# BLE_MCU_Watch_Dog_and_Reset_EEPROM_Buzze.net
KiCad netlist of a schematic drawn in Altium Designer
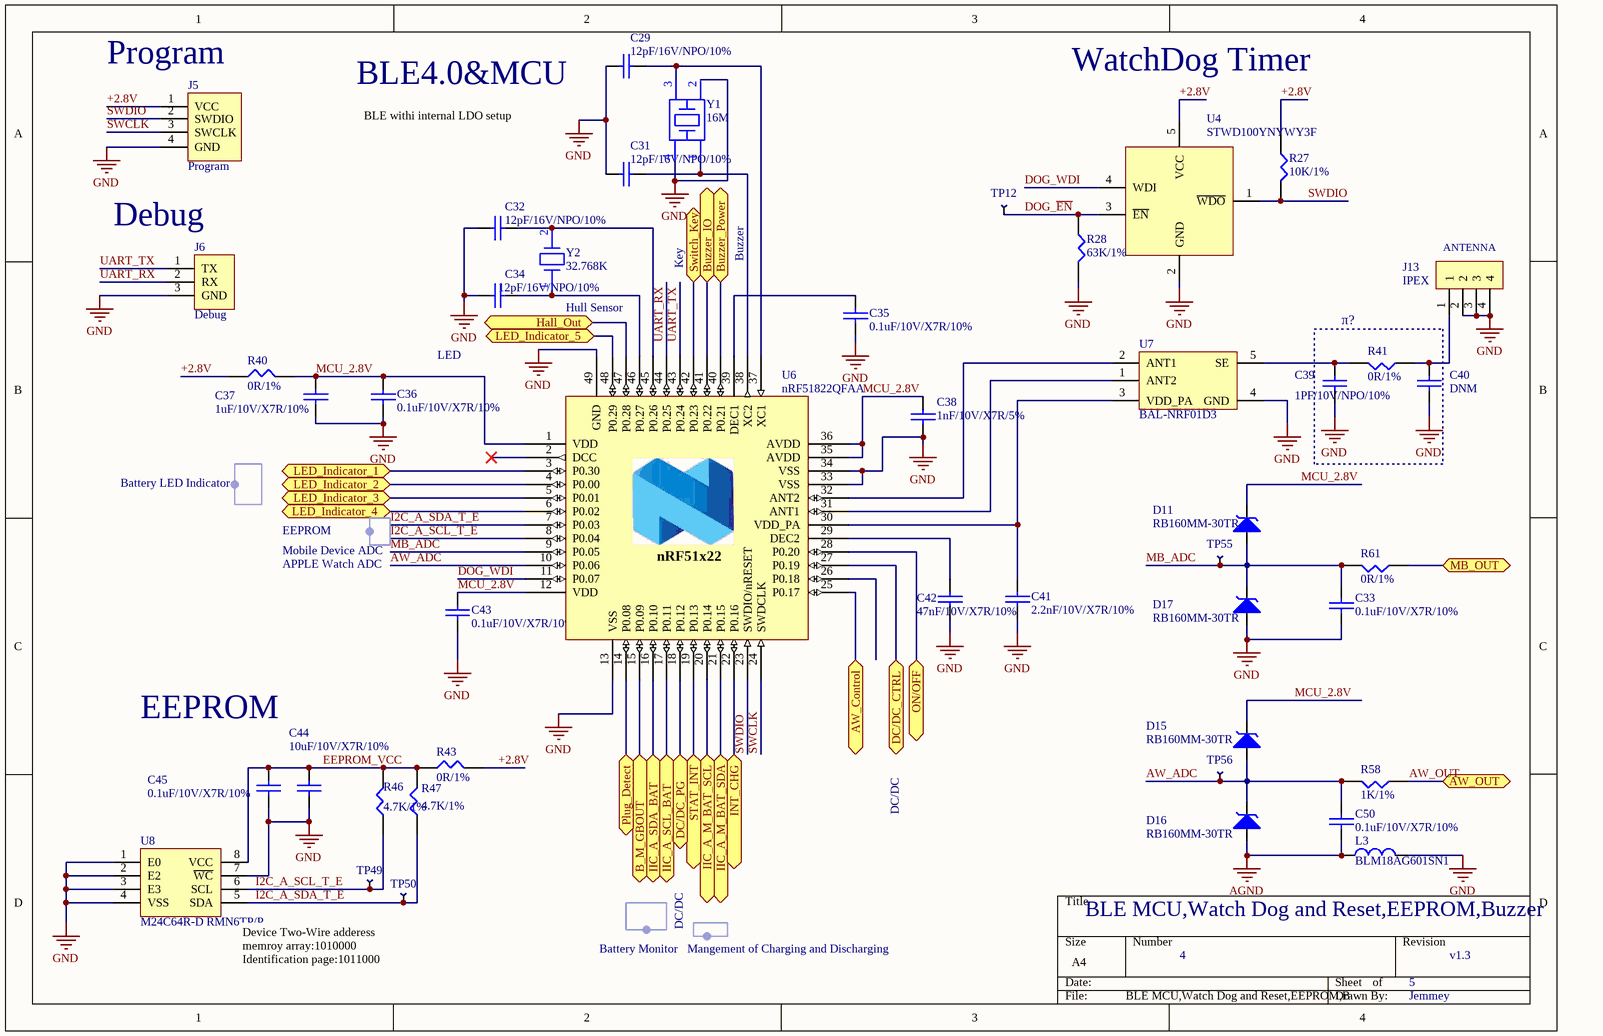
[diagram p0: BLE MCU,Watch Dog and Reset,EEPROM,Buzzer.SchDoc]

(export (version "E")
  (design (tool "Eeschema 10.0.6"))
  (components
    (comp (ref "C29")
      (value "12pF/16V/NPO/10%")
      (footprint "0402C")
      (description "厂家：Murata，型号：GRM1555C1H120JA01D")
      (libsource (lib "Amber") (part "CAP"))
    )
    (comp (ref "C31")
      (value "12pF/16V/NPO/10%")
      (footprint "0402C")
      (description "厂家：Murata，型号：GRM1555C1H120JA01D")
      (libsource (lib "Amber") (part "CAP"))
    )
    (comp (ref "C32")
      (value "12pF/16V/NPO/10%")
      (footprint "0402C")
      (description "厂家：Murata，型号：GRM1555C1H120JA01D")
      (libsource (lib "Amber") (part "CAP"))
    )
    (comp (ref "C33")
      (value "0.1uF/10V/X7R/10%")
      (footprint "0402C")
      (description "厂家：Murata，型号：GRM155R71A104KA01D")
      (libsource (lib "*") (part "CAP"))
    )
    (comp (ref "C34")
      (value "12pF/16V/NPO/10%")
      (footprint "0402C")
      (description "厂家：Murata，型号：GRM1555C1H120JA01D")
      (libsource (lib "Amber") (part "CAP"))
    )
    (comp (ref "C35")
      (value "0.1uF/10V/X7R/10%")
      (footprint "0402C")
      (description "厂家：Murata，型号：GRM155R71A104KA01D")
      (libsource (lib "Amber") (part "CAP"))
    )
    (comp (ref "C36")
      (value "0.1uF/10V/X7R/10%")
      (footprint "0402C")
      (description "厂家：Murata，型号：GRM155R71A104KA01D")
      (libsource (lib "Amber") (part "CAP"))
    )
    (comp (ref "C37")
      (value "1uF/10V/X7R/10%")
      (footprint "0402C")
      (description "厂家：Murata，型号：GRM155R61C105KA12D")
      (libsource (lib "Amber") (part "CAP"))
    )
    (comp (ref "C38")
      (value "1nF/10V/X7R/5%")
      (footprint "0402C")
      (description "厂家：Murata，型号：GRM1555C1H102JA01D")
      (libsource (lib "Amber") (part "CAP"))
    )
    (comp (ref "C39")
      (value "1PF/10V/NPO/10%")
      (footprint "0402C")
      (description "厂家：Murata，型号：GRM1555C1H1R0BA01D")
      (libsource (lib "*") (part "CAP"))
    )
    (comp (ref "C40")
      (value "DNM")
      (footprint "0402C")
      (description "None")
      (libsource (lib "*") (part "CAP"))
    )
    (comp (ref "C41")
      (value "2.2nF/10V/X7R/10%")
      (footprint "0402C")
      (description "厂家：Murata，型号：GRM155R71H222KA01D")
      (libsource (lib "Amber") (part "CAP"))
    )
    (comp (ref "C42")
      (value "47nF/10V/X7R/10%")
      (footprint "0402C")
      (description "厂家：Murata，型号：GRM155R71H473KE14D")
      (libsource (lib "Amber") (part "CAP"))
    )
    (comp (ref "C43")
      (value "0.1uF/10V/X7R/10%")
      (footprint "0402C")
      (description "厂家：Murata，型号：GRM155R71A104KA01D")
      (libsource (lib "Amber") (part "CAP"))
    )
    (comp (ref "C44")
      (value "10uF/10V/X7R/10%")
      (footprint "0603C")
      (description "厂家：Murata，型号：GRM188R61A106KE69D")
      (libsource (lib "*") (part "CAP"))
    )
    (comp (ref "C45")
      (value "0.1uF/10V/X7R/10%")
      (footprint "0402C")
      (description "厂家：Murata，型号：GRM155R71A104KA01D")
      (libsource (lib "*") (part "CAP"))
    )
    (comp (ref "C50")
      (value "0.1uF/10V/X7R/10%")
      (footprint "0402C")
      (description "厂家：Murata，型号：GRM155R71A104KA01D")
      (libsource (lib "*") (part "CAP"))
    )
    (comp (ref "D11")
      (value "RB160MM-30TR")
      (footprint "DO-214AC")
      (description "厂家：ROHM，型号：RB160MM-30TR")
      (libsource (lib "Moji_Assenbly Test") (part "Schottky barrier rectifier"))
    )
    (comp (ref "D15")
      (value "RB160MM-30TR")
      (footprint "DO-214AC")
      (description "厂家：ROHM，型号：RB160MM-30TR")
      (libsource (lib "Moji_Assenbly Test") (part "Schottky barrier rectifier"))
    )
    (comp (ref "D16")
      (value "RB160MM-30TR")
      (footprint "DO-214AC")
      (description "厂家：ROHM，型号：RB160MM-30TR")
      (libsource (lib "Moji_Assenbly Test") (part "Schottky barrier rectifier"))
    )
    (comp (ref "D17")
      (value "RB160MM-30TR")
      (footprint "DO-214AC")
      (description "厂家：ROHM，型号：RB160MM-30TR")
      (libsource (lib "Moji_Assenbly Test") (part "Schottky barrier rectifier"))
    )
    (comp (ref "J5")
      (value "Program")
      (footprint "PROGRAM - 1.27")
      (description "厂家：暂定，型号：暂定")
      (libsource (lib "Amber") (part "Program"))
    )
    (comp (ref "J6")
      (value "Debug")
      (footprint "Debug- 1.27")
      (description "厂家：暂定，型号：暂定")
      (libsource (lib "Amber") (part "Debug_1"))
    )
    (comp (ref "J13")
      (value "IPEX")
      (footprint "IPEX")
      (description "厂家：Molex，型号：73420110_sd")
      (libsource (lib "Amber") (part "ANTA"))
    )
    (comp (ref "L3")
      (value "BLM18AG601SN1")
      (footprint "0603R")
      (description "厂家：MURATA，型号：BLM18AG601SN1")
      (libsource (lib "Amber") (part "CHOKE"))
    )
    (comp (ref "R27")
      (value "10K/1%")
      (footprint "0402R")
      (description "厂家：Yageo，型号：RC0402FR-0710KL")
      (libsource (lib "*") (part "RES1"))
    )
    (comp (ref "R28")
      (value "63K/1%")
      (footprint "0402R")
      (description "厂家：Yageo，型号：RC0402FR-0763KL")
      (libsource (lib "*") (part "RES1"))
    )
    (comp (ref "R40")
      (value "0R/1%")
      (footprint "0603R")
      (description "厂家：Yageo，型号：RC0402FR-070RL")
      (libsource (lib "*") (part "RES1"))
    )
    (comp (ref "R41")
      (value "0R/1%")
      (footprint "0402R")
      (description "厂家：Yageo，型号：RC0402FR-070RL")
      (libsource (lib "*") (part "RES1"))
    )
    (comp (ref "R43")
      (value "0R/1%")
      (footprint "0603R")
      (description "厂家：Yageo，型号：RC0402FR-070RL")
      (libsource (lib "*") (part "RES1"))
    )
    (comp (ref "R46")
      (value "4.7K/1%")
      (footprint "0402R")
      (description "厂家：Yageo，型号：RC0402FR-074K7L")
      (libsource (lib "*") (part "RES1"))
    )
    (comp (ref "R47")
      (value "4.7K/1%")
      (footprint "0402R")
      (description "厂家：Yageo，型号：RC0402FR-074K7L")
      (libsource (lib "*") (part "RES1"))
    )
    (comp (ref "R58")
      (value "1K/1%")
      (footprint "0402R")
      (description "厂家：Yageo，型号：RC0402FR-070RL")
      (libsource (lib "*") (part "RES1"))
    )
    (comp (ref "R61")
      (value "0R/1%")
      (footprint "0402R")
      (description "厂家：Yageo，型号：RC0402FR-070RL")
      (libsource (lib "*") (part "RES1"))
    )
    (comp (ref "TP12")
      (value "TEST")
      (footprint "Test Pad")
      (description "Test Point")
      (libsource (lib "Amber") (part "TEST"))
    )
    (comp (ref "TP49")
      (value "TEST")
      (footprint "Test Pad")
      (description "Test Point")
      (libsource (lib "Amber") (part "TEST"))
    )
    (comp (ref "TP50")
      (value "TEST")
      (footprint "Test Pad")
      (description "Test Point")
      (libsource (lib "Amber") (part "TEST"))
    )
    (comp (ref "TP55")
      (value "TEST")
      (footprint "Test Pad")
      (description "Test Point")
      (libsource (lib "Amber") (part "TEST"))
    )
    (comp (ref "TP56")
      (value "TEST")
      (footprint "Test Pad")
      (description "Test Point")
      (libsource (lib "Amber") (part "TEST"))
    )
    (comp (ref "U4")
      (value "STWD100YNYWY3F")
      (description "厂家：ST，型号：STWD100YNYWY3F")
      (libsource (lib "Amber") (part "STWD100"))
    )
    (comp (ref "U6")
      (value "nRF51822QFAA")
      (description "厂家：Nordic，型号：Nrf51822QFAA")
      (libsource (lib "Amber") (part "nRF51822"))
    )
    (comp (ref "U7")
      (value "BAL-NRF01D3")
      (description "厂家：ST，型号：BAL-NRF01D3")
      (libsource (lib "Amber") (part "BAL-NRF01D3"))
    )
    (comp (ref "U8")
      (value "M24C64R-D RMN6TP/P")
      (footprint "SO8N")
      (description "厂家：ST，型号：M24C64R-D RMN6TP/P")
      (libsource (lib "Amber") (part "M24C64-R"))
    )
    (comp (ref "Y1")
      (value "16M")
      (footprint "XTALSMD2-2520")
      (description "厂家：EPSON，型号：Q24FA20H0004400")
      (libsource (lib "Amber_1") (part "CRYSTAL2"))
    )
    (comp (ref "Y2")
      (value "32.768K")
      (footprint "XTALSMD2-3215")
      (description "厂家：EPSON，型号：Q13FC1350000400")
      (libsource (lib "Amber") (part "CRYSTAL3"))
    )
  )
  (nets
    (net (code "1") (name "/+2.8V") (class "Default")
      (node (ref "J5") (pin "1") (pinfunction "VCC_1") (pintype "passive"))
      (node (ref "R27") (pin "1") (pinfunction "1_1") (pintype "passive"))
      (node (ref "R40") (pin "1") (pinfunction "1_1") (pintype "passive"))
      (node (ref "R43") (pin "2") (pinfunction "2_2") (pintype "passive"))
      (node (ref "U4") (pin "5") (pinfunction "VCC_5") (pintype "passive"))
    )
    (net (code "2") (name "/AW_ADC") (class "Default")
      (node (ref "C50") (pin "1") (pinfunction "1_1") (pintype "passive"))
      (node (ref "D15") (pin "2") (pinfunction "A_2") (pintype "passive"))
      (node (ref "D16") (pin "1") (pinfunction "K_1") (pintype "passive"))
      (node (ref "R58") (pin "2") (pinfunction "2_2") (pintype "passive"))
      (node (ref "TP56") (pin "1") (pinfunction "1_1") (pintype "passive"))
      (node (ref "U6") (pin "10") (pinfunction "P0.06_10") (pintype "bidirectional"))
    )
    (net (code "3") (name "/AW_Control") (class "Default")
      (node (ref "U6") (pin "25") (pinfunction "P0.17_25") (pintype "bidirectional"))
    )
    (net (code "4") (name "/AW_OUT") (class "Default")
      (node (ref "R58") (pin "1") (pinfunction "1_1") (pintype "passive"))
    )
    (net (code "5") (name "/B_M_GBOUT") (class "Default")
      (node (ref "U6") (pin "15") (pinfunction "P0.09_15") (pintype "bidirectional"))
    )
    (net (code "6") (name "/Buzzer_IO") (class "Default")
      (node (ref "U6") (pin "41") (pinfunction "P0.22_41") (pintype "bidirectional"))
    )
    (net (code "7") (name "/Buzzer_Power") (class "Default")
      (node (ref "U6") (pin "40") (pinfunction "P0.21_40") (pintype "bidirectional"))
    )
    (net (code "8") (name "/DC{slash}DC_CTRL") (class "Default")
      (node (ref "U6") (pin "27") (pinfunction "P0.19_27") (pintype "bidirectional"))
    )
    (net (code "9") (name "/DC{slash}DC_PG") (class "Default")
      (node (ref "U6") (pin "18") (pinfunction "P0.12_18") (pintype "bidirectional"))
    )
    (net (code "10") (name "/DOG_WDI") (class "Default")
      (node (ref "U4") (pin "4") (pinfunction "WDI_4") (pintype "passive"))
      (node (ref "U6") (pin "11") (pinfunction "P0.07_11") (pintype "bidirectional"))
    )
    (net (code "11") (name "/DOG_~{EN}") (class "Default")
      (node (ref "R28") (pin "1") (pinfunction "1_1") (pintype "passive"))
      (node (ref "TP12") (pin "1") (pinfunction "1_1") (pintype "passive"))
      (node (ref "U4") (pin "3") (pinfunction "~{EN}_3") (pintype "passive"))
    )
    (net (code "12") (name "/EEPROM_VCC") (class "Default")
      (node (ref "C44") (pin "1") (pinfunction "1_1") (pintype "passive"))
      (node (ref "C45") (pin "1") (pinfunction "1_1") (pintype "passive"))
      (node (ref "R43") (pin "1") (pinfunction "1_1") (pintype "passive"))
      (node (ref "R46") (pin "2") (pinfunction "2_2") (pintype "passive"))
      (node (ref "R47") (pin "2") (pinfunction "2_2") (pintype "passive"))
      (node (ref "U8") (pin "8") (pinfunction "VCC_8") (pintype "passive"))
    )
    (net (code "13") (name "/Hall_Out") (class "Default")
      (node (ref "U6") (pin "47") (pinfunction "P0.28_47") (pintype "bidirectional"))
    )
    (net (code "14") (name "/I2C_A_SCL_T_E") (class "Default")
      (node (ref "R46") (pin "1") (pinfunction "1_1") (pintype "passive"))
      (node (ref "TP49") (pin "1") (pinfunction "1_1") (pintype "passive"))
      (node (ref "U6") (pin "8") (pinfunction "P0.04_8") (pintype "bidirectional"))
      (node (ref "U8") (pin "6") (pinfunction "SCL_6") (pintype "passive"))
    )
    (net (code "15") (name "/I2C_A_SDA_T_E") (class "Default")
      (node (ref "R47") (pin "1") (pinfunction "1_1") (pintype "passive"))
      (node (ref "TP50") (pin "1") (pinfunction "1_1") (pintype "passive"))
      (node (ref "U6") (pin "7") (pinfunction "P0.03_7") (pintype "bidirectional"))
      (node (ref "U8") (pin "5") (pinfunction "SDA_5") (pintype "passive"))
    )
    (net (code "16") (name "/IIC_A_M_BAT_SCL") (class "Default")
      (node (ref "U6") (pin "20") (pinfunction "P0.14_20") (pintype "bidirectional"))
    )
    (net (code "17") (name "/IIC_A_M_BAT_SDA") (class "Default")
      (node (ref "U6") (pin "21") (pinfunction "P0.15_21") (pintype "bidirectional"))
    )
    (net (code "18") (name "/IIC_A_SCL_BAT") (class "Default")
      (node (ref "U6") (pin "17") (pinfunction "P0.11_17") (pintype "bidirectional"))
    )
    (net (code "19") (name "/IIC_A_SDA_BAT") (class "Default")
      (node (ref "U6") (pin "16") (pinfunction "P0.10_16") (pintype "bidirectional"))
    )
    (net (code "20") (name "/INT_CHG") (class "Default")
      (node (ref "U6") (pin "22") (pinfunction "P0.16_22") (pintype "bidirectional"))
    )
    (net (code "21") (name "/LED_Indicator_1") (class "Default")
      (node (ref "U6") (pin "3") (pinfunction "P0.30_3") (pintype "bidirectional"))
    )
    (net (code "22") (name "/LED_Indicator_2") (class "Default")
      (node (ref "U6") (pin "4") (pinfunction "P0.00_4") (pintype "bidirectional"))
    )
    (net (code "23") (name "/LED_Indicator_3") (class "Default")
      (node (ref "U6") (pin "5") (pinfunction "P0.01_5") (pintype "bidirectional"))
    )
    (net (code "24") (name "/LED_Indicator_4") (class "Default")
      (node (ref "U6") (pin "6") (pinfunction "P0.02_6") (pintype "bidirectional"))
    )
    (net (code "25") (name "/LED_Indicator_5") (class "Default")
      (node (ref "U6") (pin "48") (pinfunction "P0.29_48") (pintype "bidirectional"))
    )
    (net (code "26") (name "/MB_ADC") (class "Default")
      (node (ref "C33") (pin "1") (pinfunction "1_1") (pintype "passive"))
      (node (ref "D11") (pin "2") (pinfunction "A_2") (pintype "passive"))
      (node (ref "D17") (pin "1") (pinfunction "K_1") (pintype "passive"))
      (node (ref "R61") (pin "2") (pinfunction "2_2") (pintype "passive"))
      (node (ref "TP55") (pin "1") (pinfunction "1_1") (pintype "passive"))
      (node (ref "U6") (pin "9") (pinfunction "P0.05_9") (pintype "bidirectional"))
    )
    (net (code "27") (name "/MB_OUT") (class "Default")
      (node (ref "R61") (pin "1") (pinfunction "1_1") (pintype "passive"))
    )
    (net (code "28") (name "/MCU_2.8V") (class "Default")
      (node (ref "C36") (pin "2") (pinfunction "2_2") (pintype "passive"))
      (node (ref "C37") (pin "2") (pinfunction "2_2") (pintype "passive"))
      (node (ref "C38") (pin "2") (pinfunction "2_2") (pintype "passive"))
      (node (ref "C43") (pin "2") (pinfunction "2_2") (pintype "passive"))
      (node (ref "D11") (pin "1") (pinfunction "K_1") (pintype "passive"))
      (node (ref "D15") (pin "1") (pinfunction "K_1") (pintype "passive"))
      (node (ref "R40") (pin "2") (pinfunction "2_2") (pintype "passive"))
      (node (ref "U6") (pin "1") (pinfunction "VDD_1") (pintype "power_in"))
      (node (ref "U6") (pin "12") (pinfunction "VDD_12") (pintype "power_in"))
      (node (ref "U6") (pin "35") (pinfunction "AVDD_35") (pintype "power_in"))
      (node (ref "U6") (pin "36") (pinfunction "AVDD_36") (pintype "power_in"))
    )
    (net (code "29") (name "/ON{slash}OFF") (class "Default")
      (node (ref "U6") (pin "28") (pinfunction "P0.20_28") (pintype "bidirectional"))
    )
    (net (code "30") (name "/Plug_Detect") (class "Default")
      (node (ref "U6") (pin "14") (pinfunction "P0.08_14") (pintype "bidirectional"))
    )
    (net (code "31") (name "/STAT_INT") (class "Default")
      (node (ref "U6") (pin "19") (pinfunction "P0.13_19") (pintype "bidirectional"))
    )
    (net (code "32") (name "/SWCLK") (class "Default")
      (node (ref "J5") (pin "3") (pinfunction "SWCLK_3") (pintype "passive"))
      (node (ref "U6") (pin "24") (pinfunction "SWDCLK_24") (pintype "input"))
    )
    (net (code "33") (name "/SWDIO") (class "Default")
      (node (ref "J5") (pin "2") (pinfunction "SWDIO_2") (pintype "passive"))
      (node (ref "R27") (pin "2") (pinfunction "2_2") (pintype "passive"))
      (node (ref "U4") (pin "1") (pinfunction "~{WDO}_1") (pintype "passive"))
      (node (ref "U6") (pin "23") (pinfunction "SWDIO/nRESET_23") (pintype "input"))
    )
    (net (code "34") (name "/Switch_Key") (class "Default")
      (node (ref "U6") (pin "42") (pinfunction "P0.23_42") (pintype "bidirectional"))
    )
    (net (code "35") (name "/UART_RX") (class "Default")
      (node (ref "J6") (pin "2") (pinfunction "RX_2") (pintype "passive"))
      (node (ref "U6") (pin "44") (pinfunction "P0.25_44") (pintype "bidirectional"))
    )
    (net (code "36") (name "/UART_TX") (class "Default")
      (node (ref "J6") (pin "1") (pinfunction "TX_1") (pintype "passive"))
      (node (ref "U6") (pin "43") (pinfunction "P0.24_43") (pintype "bidirectional"))
    )
    (net (code "37") (name "AGND") (class "Default")
      (node (ref "C50") (pin "2") (pinfunction "2_2") (pintype "passive"))
      (node (ref "D16") (pin "2") (pinfunction "A_2") (pintype "passive"))
      (node (ref "L3") (pin "1") (pinfunction "1_1") (pintype "passive"))
    )
    (net (code "38") (name "GND") (class "Default")
      (node (ref "C29") (pin "1") (pinfunction "1_1") (pintype "passive"))
      (node (ref "C31") (pin "1") (pinfunction "1_1") (pintype "passive"))
      (node (ref "C32") (pin "1") (pinfunction "1_1") (pintype "passive"))
      (node (ref "C33") (pin "2") (pinfunction "2_2") (pintype "passive"))
      (node (ref "C34") (pin "1") (pinfunction "1_1") (pintype "passive"))
      (node (ref "C35") (pin "1") (pinfunction "1_1") (pintype "passive"))
      (node (ref "C36") (pin "1") (pinfunction "1_1") (pintype "passive"))
      (node (ref "C37") (pin "1") (pinfunction "1_1") (pintype "passive"))
      (node (ref "C38") (pin "1") (pinfunction "1_1") (pintype "passive"))
      (node (ref "C39") (pin "2") (pinfunction "2_2") (pintype "passive"))
      (node (ref "C40") (pin "2") (pinfunction "2_2") (pintype "passive"))
      (node (ref "C41") (pin "1") (pinfunction "1_1") (pintype "passive"))
      (node (ref "C42") (pin "1") (pinfunction "1_1") (pintype "passive"))
      (node (ref "C43") (pin "1") (pinfunction "1_1") (pintype "passive"))
      (node (ref "C44") (pin "2") (pinfunction "2_2") (pintype "passive"))
      (node (ref "C45") (pin "2") (pinfunction "2_2") (pintype "passive"))
      (node (ref "D17") (pin "2") (pinfunction "A_2") (pintype "passive"))
      (node (ref "J13") (pin "2") (pinfunction "2_2") (pintype "passive"))
      (node (ref "J13") (pin "3") (pinfunction "3_3") (pintype "passive"))
      (node (ref "J13") (pin "4") (pinfunction "4_4") (pintype "passive"))
      (node (ref "J5") (pin "4") (pinfunction "GND_4") (pintype "passive"))
      (node (ref "J6") (pin "3") (pinfunction "GND_3") (pintype "passive"))
      (node (ref "L3") (pin "2") (pinfunction "2_2") (pintype "passive"))
      (node (ref "R28") (pin "2") (pinfunction "2_2") (pintype "passive"))
      (node (ref "U4") (pin "2") (pinfunction "GND_2") (pintype "passive"))
      (node (ref "U6") (pin "13") (pinfunction "VSS_13") (pintype "power_in"))
      (node (ref "U6") (pin "33") (pinfunction "VSS_33") (pintype "power_in"))
      (node (ref "U6") (pin "34") (pinfunction "VSS_34") (pintype "power_in"))
      (node (ref "U6") (pin "49") (pinfunction "GND_49") (pintype "power_in"))
      (node (ref "U7") (pin "4") (pinfunction "GND_4") (pintype "passive"))
      (node (ref "U8") (pin "1") (pinfunction "E0_1") (pintype "passive"))
      (node (ref "U8") (pin "2") (pinfunction "E2_2") (pintype "passive"))
      (node (ref "U8") (pin "3") (pinfunction "E3_3") (pintype "passive"))
      (node (ref "U8") (pin "4") (pinfunction "VSS_4") (pintype "passive"))
      (node (ref "U8") (pin "7") (pinfunction "~{WC}_7") (pintype "passive"))
      (node (ref "Y1") (pin "2") (pinfunction "2_2") (pintype "passive"))
      (node (ref "Y1") (pin "4") (pinfunction "4_4") (pintype "passive"))
    )
    (net (code "39") (name "Net-(C40-Pad1)") (class "Default")
      (node (ref "C40") (pin "1") (pinfunction "1_1") (pintype "passive"))
      (node (ref "J13") (pin "1") (pinfunction "1_1") (pintype "passive"))
      (node (ref "R41") (pin "1") (pinfunction "1_1") (pintype "passive"))
    )
    (net (code "40") (name "Net-(U6-ANT1)") (class "Default")
      (node (ref "U6") (pin "31") (pinfunction "ANT1_31") (pintype "bidirectional"))
      (node (ref "U7") (pin "1") (pinfunction "ANT2_1") (pintype "passive"))
    )
    (net (code "41") (name "Net-(U6-ANT2)") (class "Default")
      (node (ref "U6") (pin "32") (pinfunction "ANT2_32") (pintype "bidirectional"))
      (node (ref "U7") (pin "2") (pinfunction "ANT1_2") (pintype "passive"))
    )
    (net (code "42") (name "Net-(U6-DEC1)") (class "Default")
      (node (ref "C35") (pin "2") (pinfunction "2_2") (pintype "passive"))
      (node (ref "U6") (pin "39") (pinfunction "DEC1_39") (pintype "power_in"))
    )
    (net (code "43") (name "Net-(U6-DEC2)") (class "Default")
      (node (ref "C42") (pin "2") (pinfunction "2_2") (pintype "passive"))
      (node (ref "U6") (pin "29") (pinfunction "DEC2_29") (pintype "power_in"))
    )
    (net (code "44") (name "Net-(U6-P0.26)") (class "Default")
      (node (ref "C32") (pin "2") (pinfunction "2_2") (pintype "passive"))
      (node (ref "U6") (pin "45") (pinfunction "P0.26_45") (pintype "bidirectional"))
      (node (ref "Y2") (pin "2") (pinfunction "2_2") (pintype "passive"))
    )
    (net (code "45") (name "Net-(U6-P0.27)") (class "Default")
      (node (ref "C34") (pin "2") (pinfunction "2_2") (pintype "passive"))
      (node (ref "U6") (pin "46") (pinfunction "P0.27_46") (pintype "bidirectional"))
      (node (ref "Y2") (pin "1") (pinfunction "1_1") (pintype "passive"))
    )
    (net (code "46") (name "Net-(U6-VDD_PA)") (class "Default")
      (node (ref "C41") (pin "2") (pinfunction "2_2") (pintype "passive"))
      (node (ref "U6") (pin "30") (pinfunction "VDD_PA_30") (pintype "power_in"))
      (node (ref "U7") (pin "3") (pinfunction "VDD_PA_3") (pintype "passive"))
    )
    (net (code "47") (name "Net-(U6-XC1)") (class "Default")
      (node (ref "C29") (pin "2") (pinfunction "2_2") (pintype "passive"))
      (node (ref "U6") (pin "37") (pinfunction "XC1_37") (pintype "input"))
      (node (ref "Y1") (pin "3") (pinfunction "3_3") (pintype "passive"))
    )
    (net (code "48") (name "Net-(U6-XC2)") (class "Default")
      (node (ref "C31") (pin "2") (pinfunction "2_2") (pintype "passive"))
      (node (ref "U6") (pin "38") (pinfunction "XC2_38") (pintype "output"))
      (node (ref "Y1") (pin "1") (pinfunction "1_1") (pintype "passive"))
    )
    (net (code "49") (name "Net-(U7-SE)") (class "Default")
      (node (ref "C39") (pin "1") (pinfunction "1_1") (pintype "passive"))
      (node (ref "R41") (pin "2") (pinfunction "2_2") (pintype "passive"))
      (node (ref "U7") (pin "5") (pinfunction "SE_5") (pintype "passive"))
    )
    (net (code "50") (name "unconnected-(U6-DCC-Pad2)") (class "Default")
      (node (ref "U6") (pin "2") (pinfunction "DCC_2") (pintype "output+no_connect"))
    )
    (net (code "51") (name "unconnected-(U6-P0.18-Pad26)") (class "Default")
      (node (ref "U6") (pin "26") (pinfunction "P0.18_26") (pintype "bidirectional"))
    )
  )
)
